# esp_altimeter_evo1.net
KiCad netlist of a schematic drawn in Altium Designer
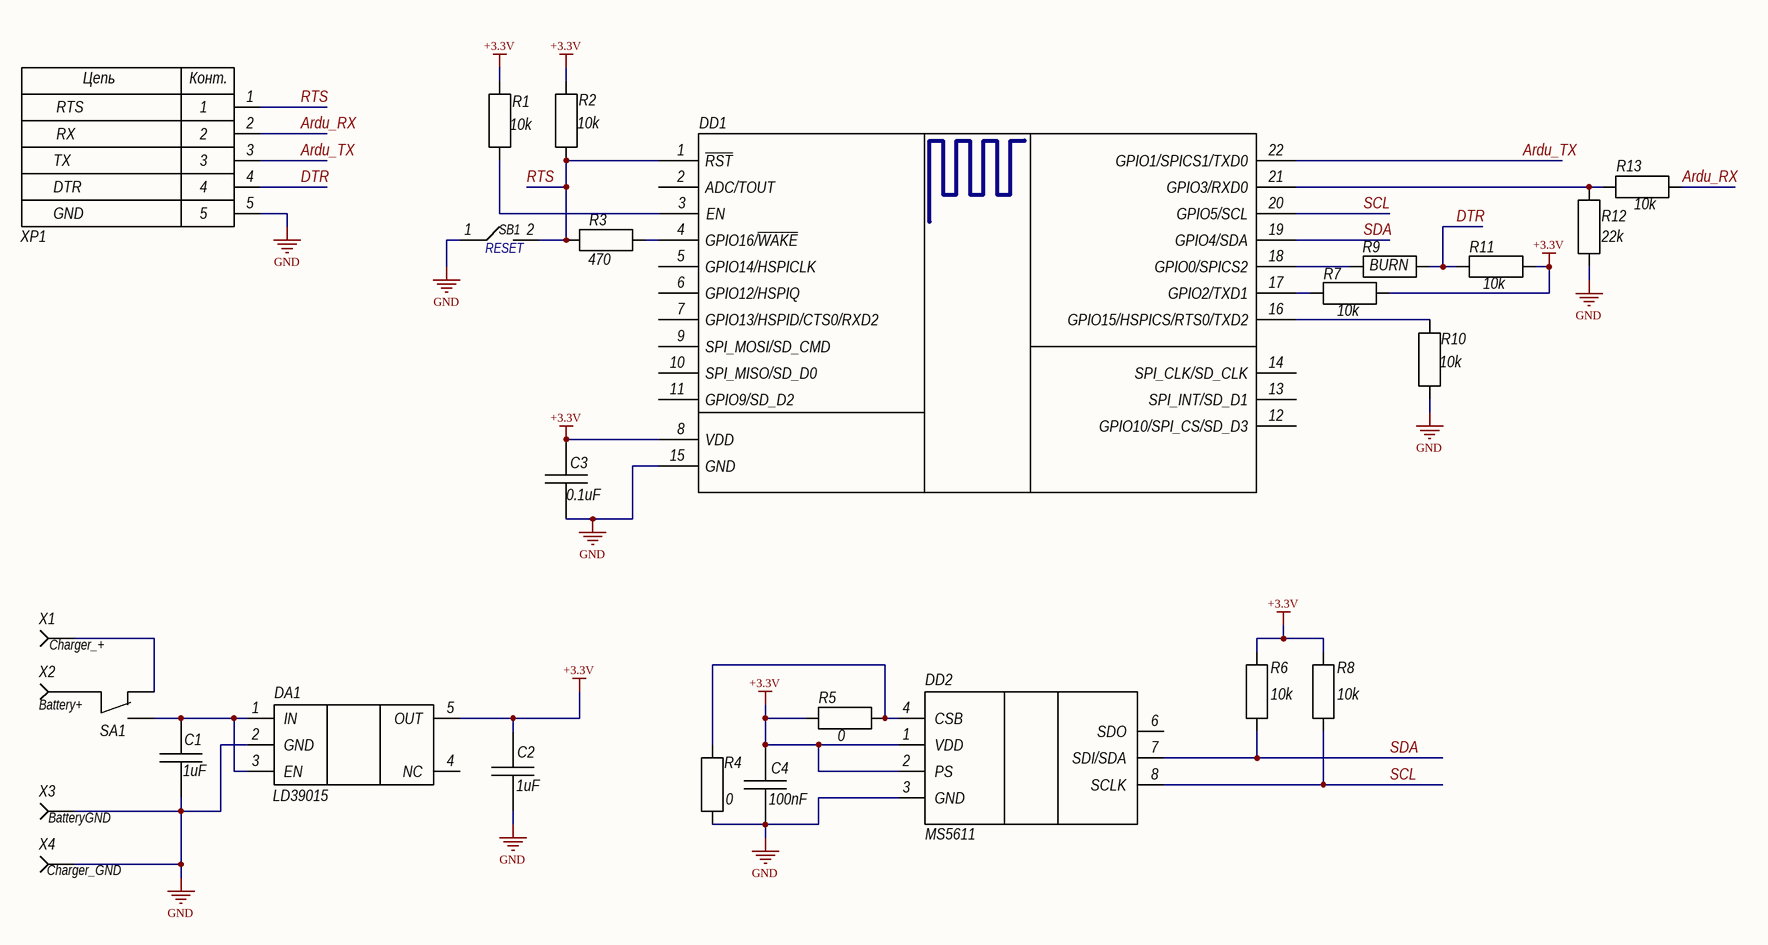
[diagram p0: esp_altimeter_evo1.SchDoc]

(export (version "E")
  (design (tool "Eeschema 10.0.6"))
  (components
    (comp (ref "C1")
      (value "1uF")
      (footprint "CAP EIA 0603")
      (fields (field (name "Comment") "Cap EIA 0603"))
      (libsource (lib "Altium_Capicators_Lib") (part "Cap EIA 0603"))
    )
    (comp (ref "C2")
      (value "1uF")
      (footprint "CAP EIA 0603")
      (fields (field (name "Comment") "Cap EIA 0603"))
      (libsource (lib "Altium_Capicators_Lib") (part "Cap EIA 0603"))
    )
    (comp (ref "C3")
      (value "0.1uF")
      (footprint "CAP EIA 0603")
      (fields (field (name "Comment") "Cap EIA 0603"))
      (libsource (lib "Altium_Capicators_Lib") (part "Cap EIA 0603"))
    )
    (comp (ref "C4")
      (value "100nF")
      (footprint "CAP EIA 0603")
      (fields (field (name "Comment") "Cap EIA 0603"))
      (libsource (lib "Altium_Capicators_Lib") (part "Cap EIA 0603"))
    )
    (comp (ref "DA1")
      (value "LD39015")
      (footprint "SOT23-5L")
      (libsource (lib "Altium_Power_System_Lib") (part "LD39015"))
    )
    (comp (ref "DD1")
      (value "ESP8266 ESP-12E-RU")
      (footprint "ESP8266 ESP-12-E")
      (fields (field (name "MANUFACTURER") "Espressif"))
      (libsource (lib "Altium_Microcontrollers_Lib") (part "ESP8266 ESP-12E-RU"))
    )
    (comp (ref "DD2")
      (value "MS5611")
      (footprint "MS5611")
      (libsource (lib "Altium_Sensors_Lib") (part "MS5611"))
    )
    (comp (ref "R1")
      (value "10k")
      (footprint "RES EIA 0603")
      (fields (field (name "Comment") "Res EIA 0603"))
      (libsource (lib "Altium_Resistors_Lib") (part "Res EIA 0603"))
    )
    (comp (ref "R2")
      (value "10k")
      (footprint "RES EIA 0603")
      (fields (field (name "Comment") "Res EIA 0603"))
      (libsource (lib "Altium_Resistors_Lib") (part "Res EIA 0603"))
    )
    (comp (ref "R3")
      (value "470")
      (footprint "RES EIA 0603")
      (fields (field (name "Comment") "Res EIA 0603"))
      (libsource (lib "Altium_Resistors_Lib") (part "Res EIA 0603"))
    )
    (comp (ref "R4")
      (value "0")
      (footprint "RES EIA 0402")
      (fields (field (name "Comment") "Res EIA 0402"))
      (libsource (lib "Altium_Resistors_Lib") (part "Res EIA 0402"))
    )
    (comp (ref "R5")
      (value "0")
      (footprint "RES EIA 0402")
      (fields (field (name "Comment") "Res EIA 0402"))
      (libsource (lib "Altium_Resistors_Lib") (part "Res EIA 0402"))
    )
    (comp (ref "R6")
      (value "10k")
      (footprint "RES EIA 0603")
      (fields (field (name "Comment") "Res EIA 0603"))
      (libsource (lib "Altium_Resistors_Lib") (part "Res EIA 0603"))
    )
    (comp (ref "R7")
      (value "10k")
      (footprint "RES EIA 0603")
      (fields (field (name "Comment") "Res EIA 0603"))
      (libsource (lib "Altium_Resistors_Lib") (part "Res EIA 0603"))
    )
    (comp (ref "R8")
      (value "10k")
      (footprint "RES EIA 0603")
      (fields (field (name "Comment") "Res EIA 0603"))
      (libsource (lib "Altium_Resistors_Lib") (part "Res EIA 0603"))
    )
    (comp (ref "R9")
      (value "Res EIA 0603")
      (footprint "RES EIA 0603")
      (fields (field (name "NAME") "BURN"))
      (libsource (lib "Altium_Resistors_Lib") (part "Res EIA 0603"))
    )
    (comp (ref "R10")
      (value "10k")
      (footprint "RES EIA 0603")
      (fields (field (name "Comment") "Res EIA 0603"))
      (libsource (lib "Altium_Resistors_Lib") (part "Res EIA 0603"))
    )
    (comp (ref "R11")
      (value "10k")
      (footprint "RES EIA 0603")
      (fields (field (name "Comment") "Res EIA 0603"))
      (libsource (lib "Altium_Resistors_Lib") (part "Res EIA 0603"))
    )
    (comp (ref "R12")
      (value "22k")
      (footprint "RES EIA 0603")
      (fields (field (name "Comment") "Res EIA 0603"))
      (libsource (lib "Altium_Resistors_Lib") (part "Res EIA 0603"))
    )
    (comp (ref "R13")
      (value "10k")
      (footprint "RES EIA 0603")
      (fields (field (name "Comment") "Res EIA 0603"))
      (libsource (lib "Altium_Resistors_Lib") (part "Res EIA 0603"))
    )
    (comp (ref "SA1")
      (value "IS-1290")
      (footprint "IS-1290F")
      (libsource (lib "Altium_Switchers_Lib") (part "IS-1290"))
    )
    (comp (ref "SB1")
      (value "RESET")
      (footprint "SB_Pad")
      (libsource (lib "Altium_Connectors_Lib") (part "SB_Pad"))
    )
    (comp (ref "X1")
      (value "Charger_+")
      (footprint "Surface_Pad")
      (libsource (lib "Altium_Connectors_Lib") (part "Surface_Pad"))
    )
    (comp (ref "X2")
      (value "Battery+")
      (footprint "Surface_Pad")
      (libsource (lib "Altium_Connectors_Lib") (part "Surface_Pad"))
    )
    (comp (ref "X3")
      (value "BatteryGND")
      (footprint "Surface_Pad")
      (libsource (lib "Altium_Connectors_Lib") (part "Surface_Pad"))
    )
    (comp (ref "X4")
      (value "Charger_GND")
      (footprint "Surface_Pad")
      (libsource (lib "Altium_Connectors_Lib") (part "Surface_Pad"))
    )
    (comp (ref "XP1")
      (value "BM05B-SRSS-TB")
      (footprint "BM05B-SRSS-TB")
      (description "5-Pin Angle Connector")
      (fields (field (name "MANUFACTURER") "JST"))
      (libsource (lib "Altium_Connectors_Lib") (part "BM05B-SRSS-TB"))
    )
  )
  (nets
    (net (code "1") (name "+3.3V") (class "Default")
      (node (ref "C2") (pin "2") (pinfunction "2_2") (pintype "passive"))
      (node (ref "C3") (pin "2") (pinfunction "2_2") (pintype "passive"))
      (node (ref "C4") (pin "2") (pinfunction "2_2") (pintype "passive"))
      (node (ref "DA1") (pin "5") (pinfunction "OUT_5") (pintype "passive"))
      (node (ref "DD1") (pin "8") (pinfunction "VDD_8") (pintype "passive"))
      (node (ref "DD2") (pin "1") (pinfunction "VDD_1") (pintype "passive"))
      (node (ref "DD2") (pin "2") (pinfunction "PS_2") (pintype "passive"))
      (node (ref "R1") (pin "2") (pinfunction "2_2") (pintype "passive"))
      (node (ref "R11") (pin "2") (pinfunction "2_2") (pintype "passive"))
      (node (ref "R2") (pin "2") (pinfunction "2_2") (pintype "passive"))
      (node (ref "R5") (pin "1") (pinfunction "1_1") (pintype "passive"))
      (node (ref "R6") (pin "2") (pinfunction "2_2") (pintype "passive"))
      (node (ref "R7") (pin "2") (pinfunction "2_2") (pintype "passive"))
      (node (ref "R8") (pin "2") (pinfunction "2_2") (pintype "passive"))
    )
    (net (code "2") (name "/Ardu_RX") (class "Default")
      (node (ref "R13") (pin "2") (pinfunction "2_2") (pintype "passive"))
      (node (ref "XP1") (pin "2") (pinfunction "2_2") (pintype "passive"))
    )
    (net (code "3") (name "/Ardu_TX") (class "Default")
      (node (ref "DD1") (pin "22") (pinfunction "GPIO1/SPICS1/TXD0_22") (pintype "passive"))
      (node (ref "XP1") (pin "3") (pinfunction "3_3") (pintype "passive"))
    )
    (net (code "4") (name "/DTR") (class "Default")
      (node (ref "R11") (pin "1") (pinfunction "1_1") (pintype "passive"))
      (node (ref "R9") (pin "2") (pinfunction "2_2") (pintype "passive"))
      (node (ref "XP1") (pin "4") (pinfunction "4_4") (pintype "passive"))
    )
    (net (code "5") (name "/RTS") (class "Default")
      (node (ref "DD1") (pin "1") (pinfunction "~{RST}_1") (pintype "passive"))
      (node (ref "R2") (pin "1") (pinfunction "1_1") (pintype "passive"))
      (node (ref "R3") (pin "1") (pinfunction "1_1") (pintype "passive"))
      (node (ref "SB1") (pin "2") (pinfunction "OUT_2") (pintype "passive"))
      (node (ref "XP1") (pin "1") (pinfunction "1_1") (pintype "passive"))
    )
    (net (code "6") (name "/SCL") (class "Default")
      (node (ref "DD1") (pin "20") (pinfunction "GPIO5/SCL_20") (pintype "passive"))
      (node (ref "DD2") (pin "8") (pinfunction "SCLK_8") (pintype "passive"))
      (node (ref "R8") (pin "1") (pinfunction "1_1") (pintype "passive"))
    )
    (net (code "7") (name "/SDA") (class "Default")
      (node (ref "DD1") (pin "19") (pinfunction "GPIO4/SDA_19") (pintype "passive"))
      (node (ref "DD2") (pin "7") (pinfunction "SDI/SDA_7") (pintype "passive"))
      (node (ref "R6") (pin "1") (pinfunction "1_1") (pintype "passive"))
    )
    (net (code "8") (name "GND") (class "Default")
      (node (ref "C1") (pin "1") (pinfunction "1_1") (pintype "passive"))
      (node (ref "C2") (pin "1") (pinfunction "1_1") (pintype "passive"))
      (node (ref "C3") (pin "1") (pinfunction "1_1") (pintype "passive"))
      (node (ref "C4") (pin "1") (pinfunction "1_1") (pintype "passive"))
      (node (ref "DA1") (pin "2") (pinfunction "GND_2") (pintype "passive"))
      (node (ref "DD1") (pin "15") (pinfunction "GND_15") (pintype "passive"))
      (node (ref "DD2") (pin "3") (pinfunction "GND_3") (pintype "passive"))
      (node (ref "R10") (pin "1") (pinfunction "1_1") (pintype "passive"))
      (node (ref "R12") (pin "1") (pinfunction "1_1") (pintype "passive"))
      (node (ref "R4") (pin "1") (pinfunction "1_1") (pintype "passive"))
      (node (ref "SB1") (pin "1") (pinfunction "OUT_1") (pintype "passive"))
      (node (ref "X3") (pin "1") (pinfunction "1_1") (pintype "passive"))
      (node (ref "X4") (pin "1") (pinfunction "1_1") (pintype "passive"))
      (node (ref "XP1") (pin "5") (pinfunction "5_5") (pintype "passive"))
    )
    (net (code "9") (name "Net-(DA1-EN)") (class "Default")
      (node (ref "C1") (pin "2") (pinfunction "2_2") (pintype "passive"))
      (node (ref "DA1") (pin "1") (pinfunction "IN_1") (pintype "passive"))
      (node (ref "DA1") (pin "3") (pinfunction "EN_3") (pintype "passive"))
      (node (ref "SA1") (pin "1") (pintype "passive"))
    )
    (net (code "10") (name "Net-(DD1-EN)") (class "Default")
      (node (ref "DD1") (pin "3") (pinfunction "EN_3") (pintype "passive"))
      (node (ref "R1") (pin "1") (pinfunction "1_1") (pintype "passive"))
    )
    (net (code "11") (name "Net-(DD1-GPIO0{slash}SPICS2)") (class "Default")
      (node (ref "DD1") (pin "18") (pinfunction "GPIO0/SPICS2_18") (pintype "passive"))
      (node (ref "R9") (pin "1") (pinfunction "1_1") (pintype "passive"))
    )
    (net (code "12") (name "Net-(DD1-GPIO2{slash}TXD1)") (class "Default")
      (node (ref "DD1") (pin "17") (pinfunction "GPIO2/TXD1_17") (pintype "passive"))
      (node (ref "R7") (pin "1") (pinfunction "1_1") (pintype "passive"))
    )
    (net (code "13") (name "Net-(DD1-GPIO3{slash}RXD0)") (class "Default")
      (node (ref "DD1") (pin "21") (pinfunction "GPIO3/RXD0_21") (pintype "passive"))
      (node (ref "R12") (pin "2") (pinfunction "2_2") (pintype "passive"))
      (node (ref "R13") (pin "1") (pinfunction "1_1") (pintype "passive"))
    )
    (net (code "14") (name "Net-(DD1-GPIO15{slash}HSPICS{slash}RTS0{slash}TXD2)") (class "Default")
      (node (ref "DD1") (pin "16") (pinfunction "GPIO15/HSPICS/RTS0/TXD2_16") (pintype "passive"))
      (node (ref "R10") (pin "2") (pinfunction "2_2") (pintype "passive"))
    )
    (net (code "15") (name "Net-(DD1-GPIO16{slash}~{WAKE})") (class "Default")
      (node (ref "DD1") (pin "4") (pinfunction "GPIO16/~{WAKE}_4") (pintype "passive"))
      (node (ref "R3") (pin "2") (pinfunction "2_2") (pintype "passive"))
    )
    (net (code "16") (name "Net-(DD2-CSB-Pad4)") (class "Default")
      (node (ref "DD2") (pin "4") (pinfunction "CSB_4") (pintype "passive"))
      (node (ref "R4") (pin "2") (pinfunction "2_2") (pintype "passive"))
      (node (ref "R5") (pin "2") (pinfunction "2_2") (pintype "passive"))
    )
    (net (code "17") (name "Net-(SA1-Pad2)") (class "Default")
      (node (ref "SA1") (pin "2") (pintype "passive"))
      (node (ref "X2") (pin "1") (pinfunction "1_1") (pintype "passive"))
    )
    (net (code "18") (name "Net-(SA1-Pad3)") (class "Default")
      (node (ref "SA1") (pin "3") (pintype "passive"))
      (node (ref "X1") (pin "1") (pinfunction "1_1") (pintype "passive"))
    )
    (net (code "19") (name "unconnected-(DA1-NC-Pad4)") (class "Default")
      (node (ref "DA1") (pin "4") (pinfunction "NC_4") (pintype "passive"))
    )
    (net (code "20") (name "unconnected-(DD1-ADC{slash}TOUT-Pad2)") (class "Default")
      (node (ref "DD1") (pin "2") (pinfunction "ADC/TOUT_2") (pintype "passive"))
    )
    (net (code "21") (name "unconnected-(DD1-GPIO9{slash}SD_D2-Pad11)") (class "Default")
      (node (ref "DD1") (pin "11") (pinfunction "GPIO9/SD_D2_11") (pintype "passive"))
    )
    (net (code "22") (name "unconnected-(DD1-GPIO10{slash}SPI_CS{slash}SD_D3-Pad12)") (class "Default")
      (node (ref "DD1") (pin "12") (pinfunction "GPIO10/SPI_CS/SD_D3_12") (pintype "passive"))
    )
    (net (code "23") (name "unconnected-(DD1-GPIO12{slash}HSPIQ-Pad6)") (class "Default")
      (node (ref "DD1") (pin "6") (pinfunction "GPIO12/HSPIQ_6") (pintype "passive"))
    )
    (net (code "24") (name "unconnected-(DD1-GPIO13{slash}HSPID{slash}CTS0{slash}RXD2-Pad7)") (class "Default")
      (node (ref "DD1") (pin "7") (pinfunction "GPIO13/HSPID/CTS0/RXD2_7") (pintype "passive"))
    )
    (net (code "25") (name "unconnected-(DD1-GPIO14{slash}HSPICLK-Pad5)") (class "Default")
      (node (ref "DD1") (pin "5") (pinfunction "GPIO14/HSPICLK_5") (pintype "passive"))
    )
    (net (code "26") (name "unconnected-(DD1-SPI_CLK{slash}SD_CLK-Pad14)") (class "Default")
      (node (ref "DD1") (pin "14") (pinfunction "SPI_CLK/SD_CLK_14") (pintype "passive"))
    )
    (net (code "27") (name "unconnected-(DD1-SPI_INT{slash}SD_D1-Pad13)") (class "Default")
      (node (ref "DD1") (pin "13") (pinfunction "SPI_INT/SD_D1_13") (pintype "passive"))
    )
    (net (code "28") (name "unconnected-(DD1-SPI_MISO{slash}SD_D0-Pad10)") (class "Default")
      (node (ref "DD1") (pin "10") (pinfunction "SPI_MISO/SD_D0_10") (pintype "passive"))
    )
    (net (code "29") (name "unconnected-(DD1-SPI_MOSI{slash}SD_CMD-Pad9)") (class "Default")
      (node (ref "DD1") (pin "9") (pinfunction "SPI_MOSI/SD_CMD_9") (pintype "passive"))
    )
    (net (code "30") (name "unconnected-(DD2-CSB-Pad5)") (class "Default")
      (node (ref "DD2") (pin "5") (pinfunction "CSB_5") (pintype "passive"))
    )
    (net (code "31") (name "unconnected-(DD2-SDO-Pad6)") (class "Default")
      (node (ref "DD2") (pin "6") (pinfunction "SDO_6") (pintype "passive"))
    )
  )
)
